# ETH_module.net
KiCad netlist of a schematic drawn in EAGLE
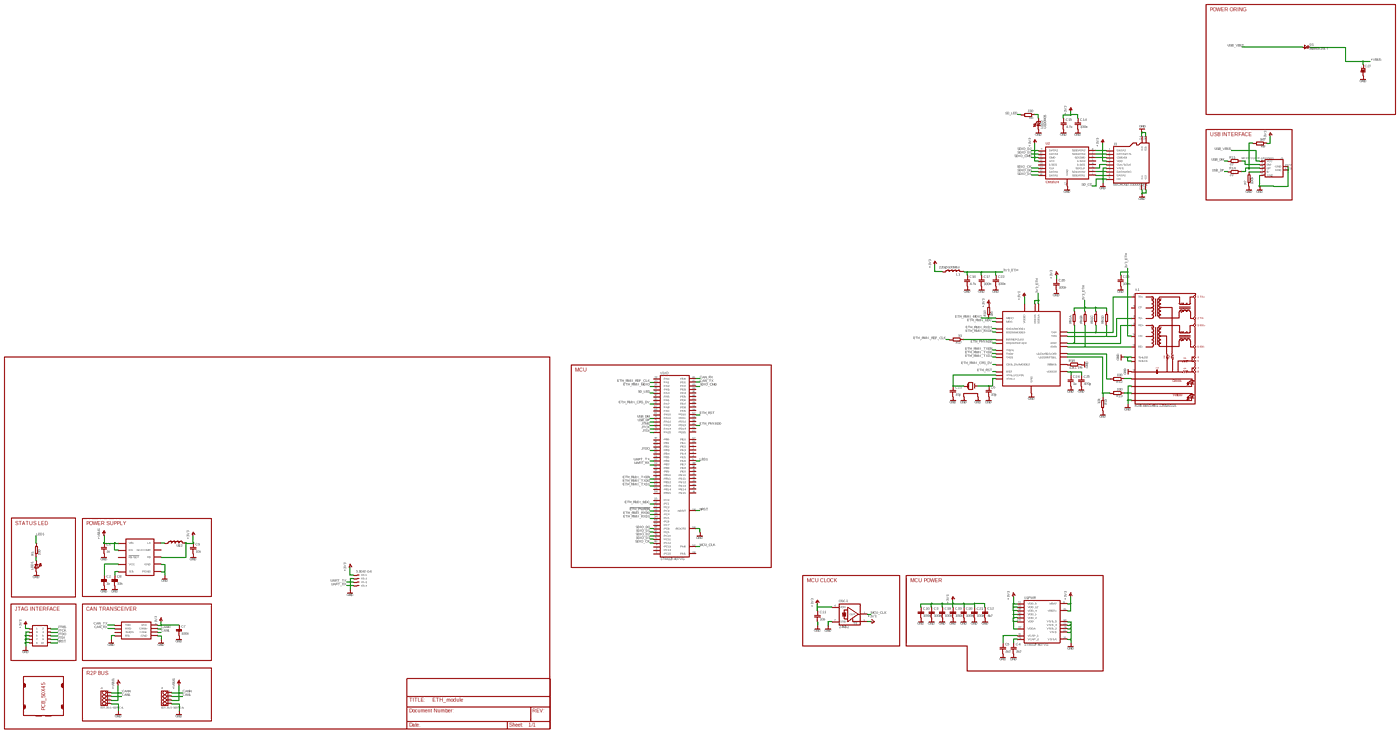
[diagram p0: schematic, sheet 1, overview]
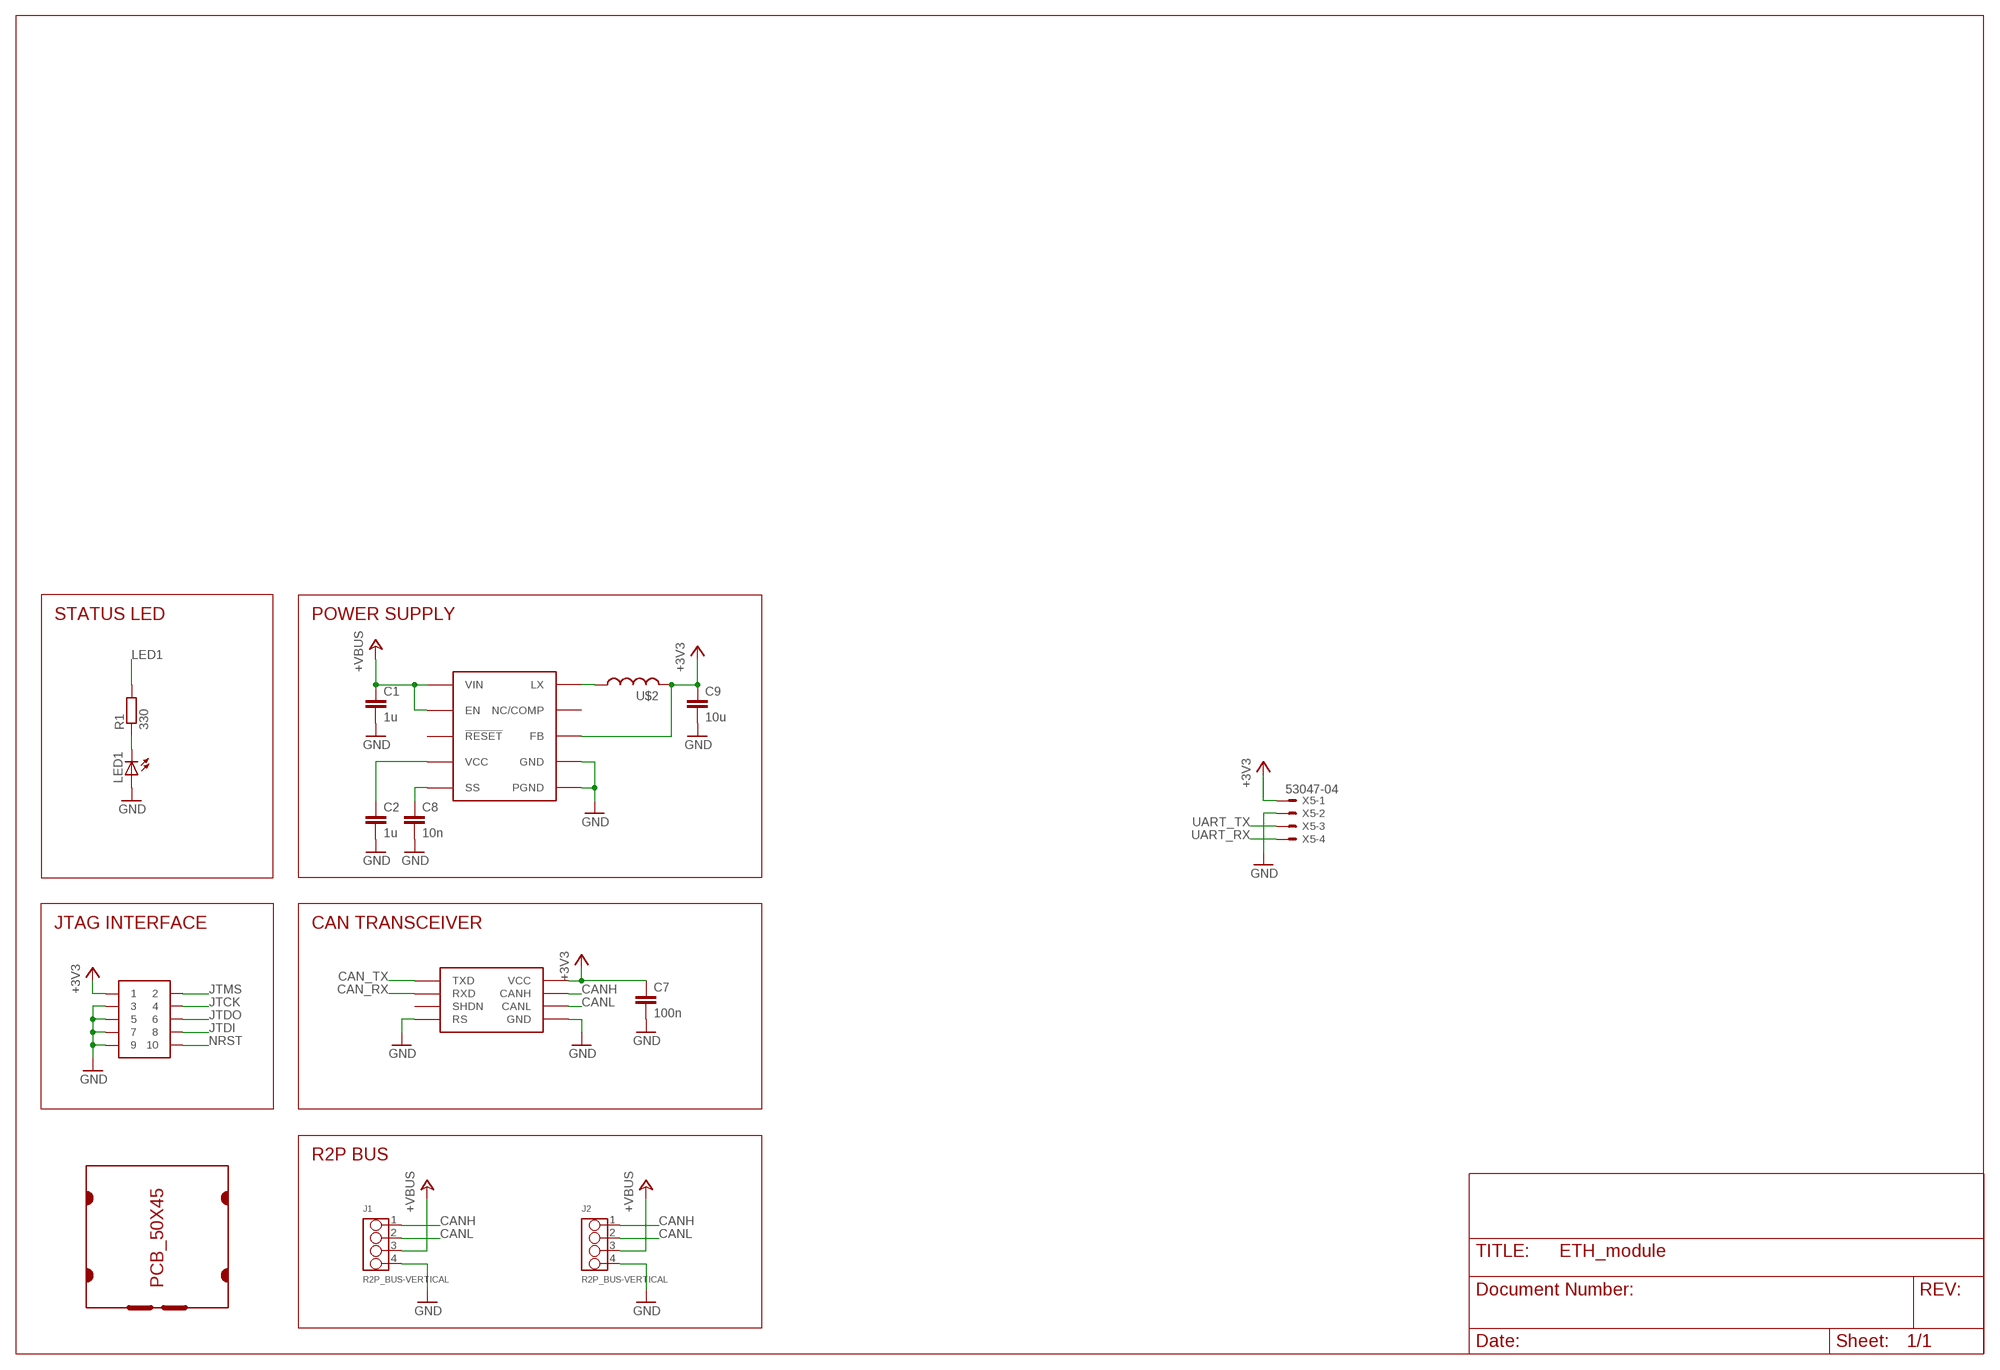
[diagram p1: schematic, sheet 1, part 1 of 4]
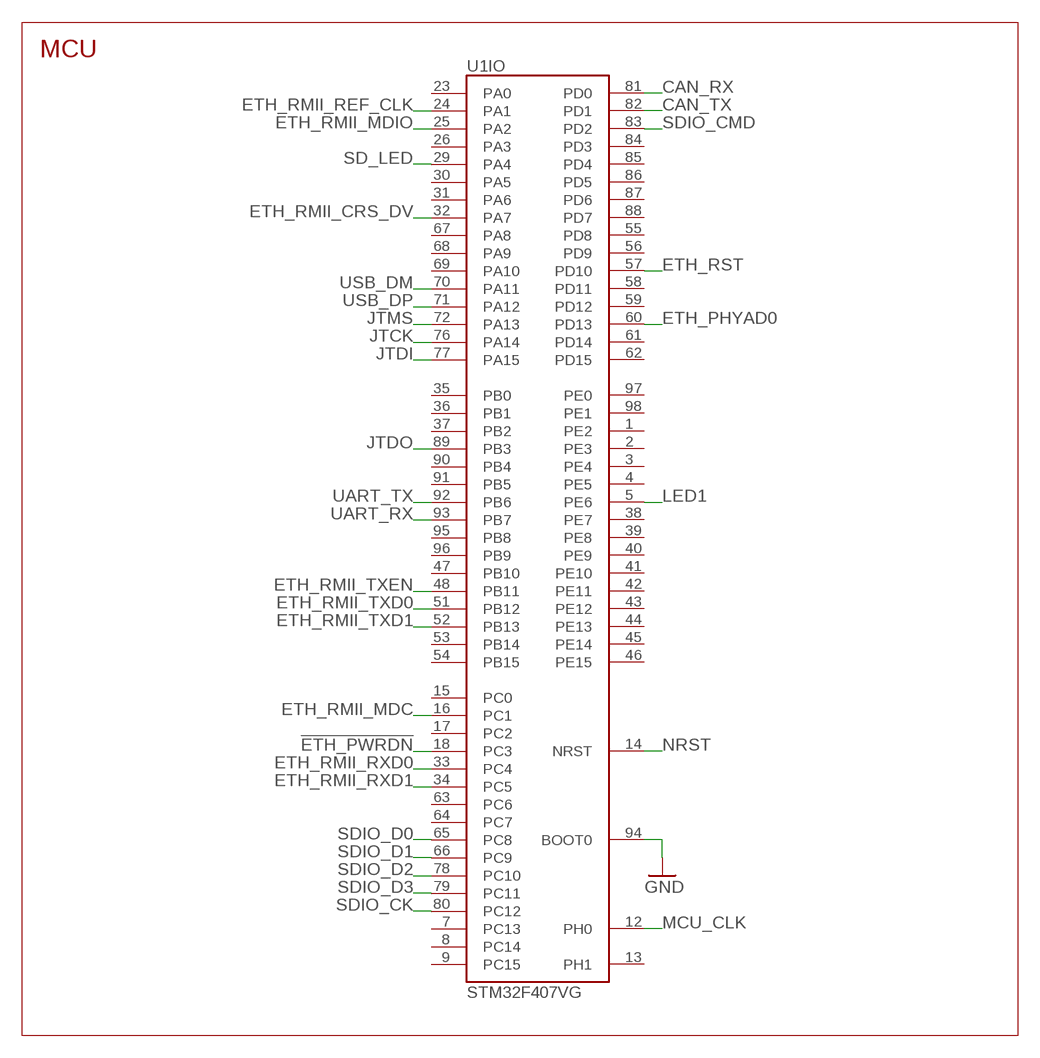
[diagram p2: schematic, sheet 1, part 2 of 4]
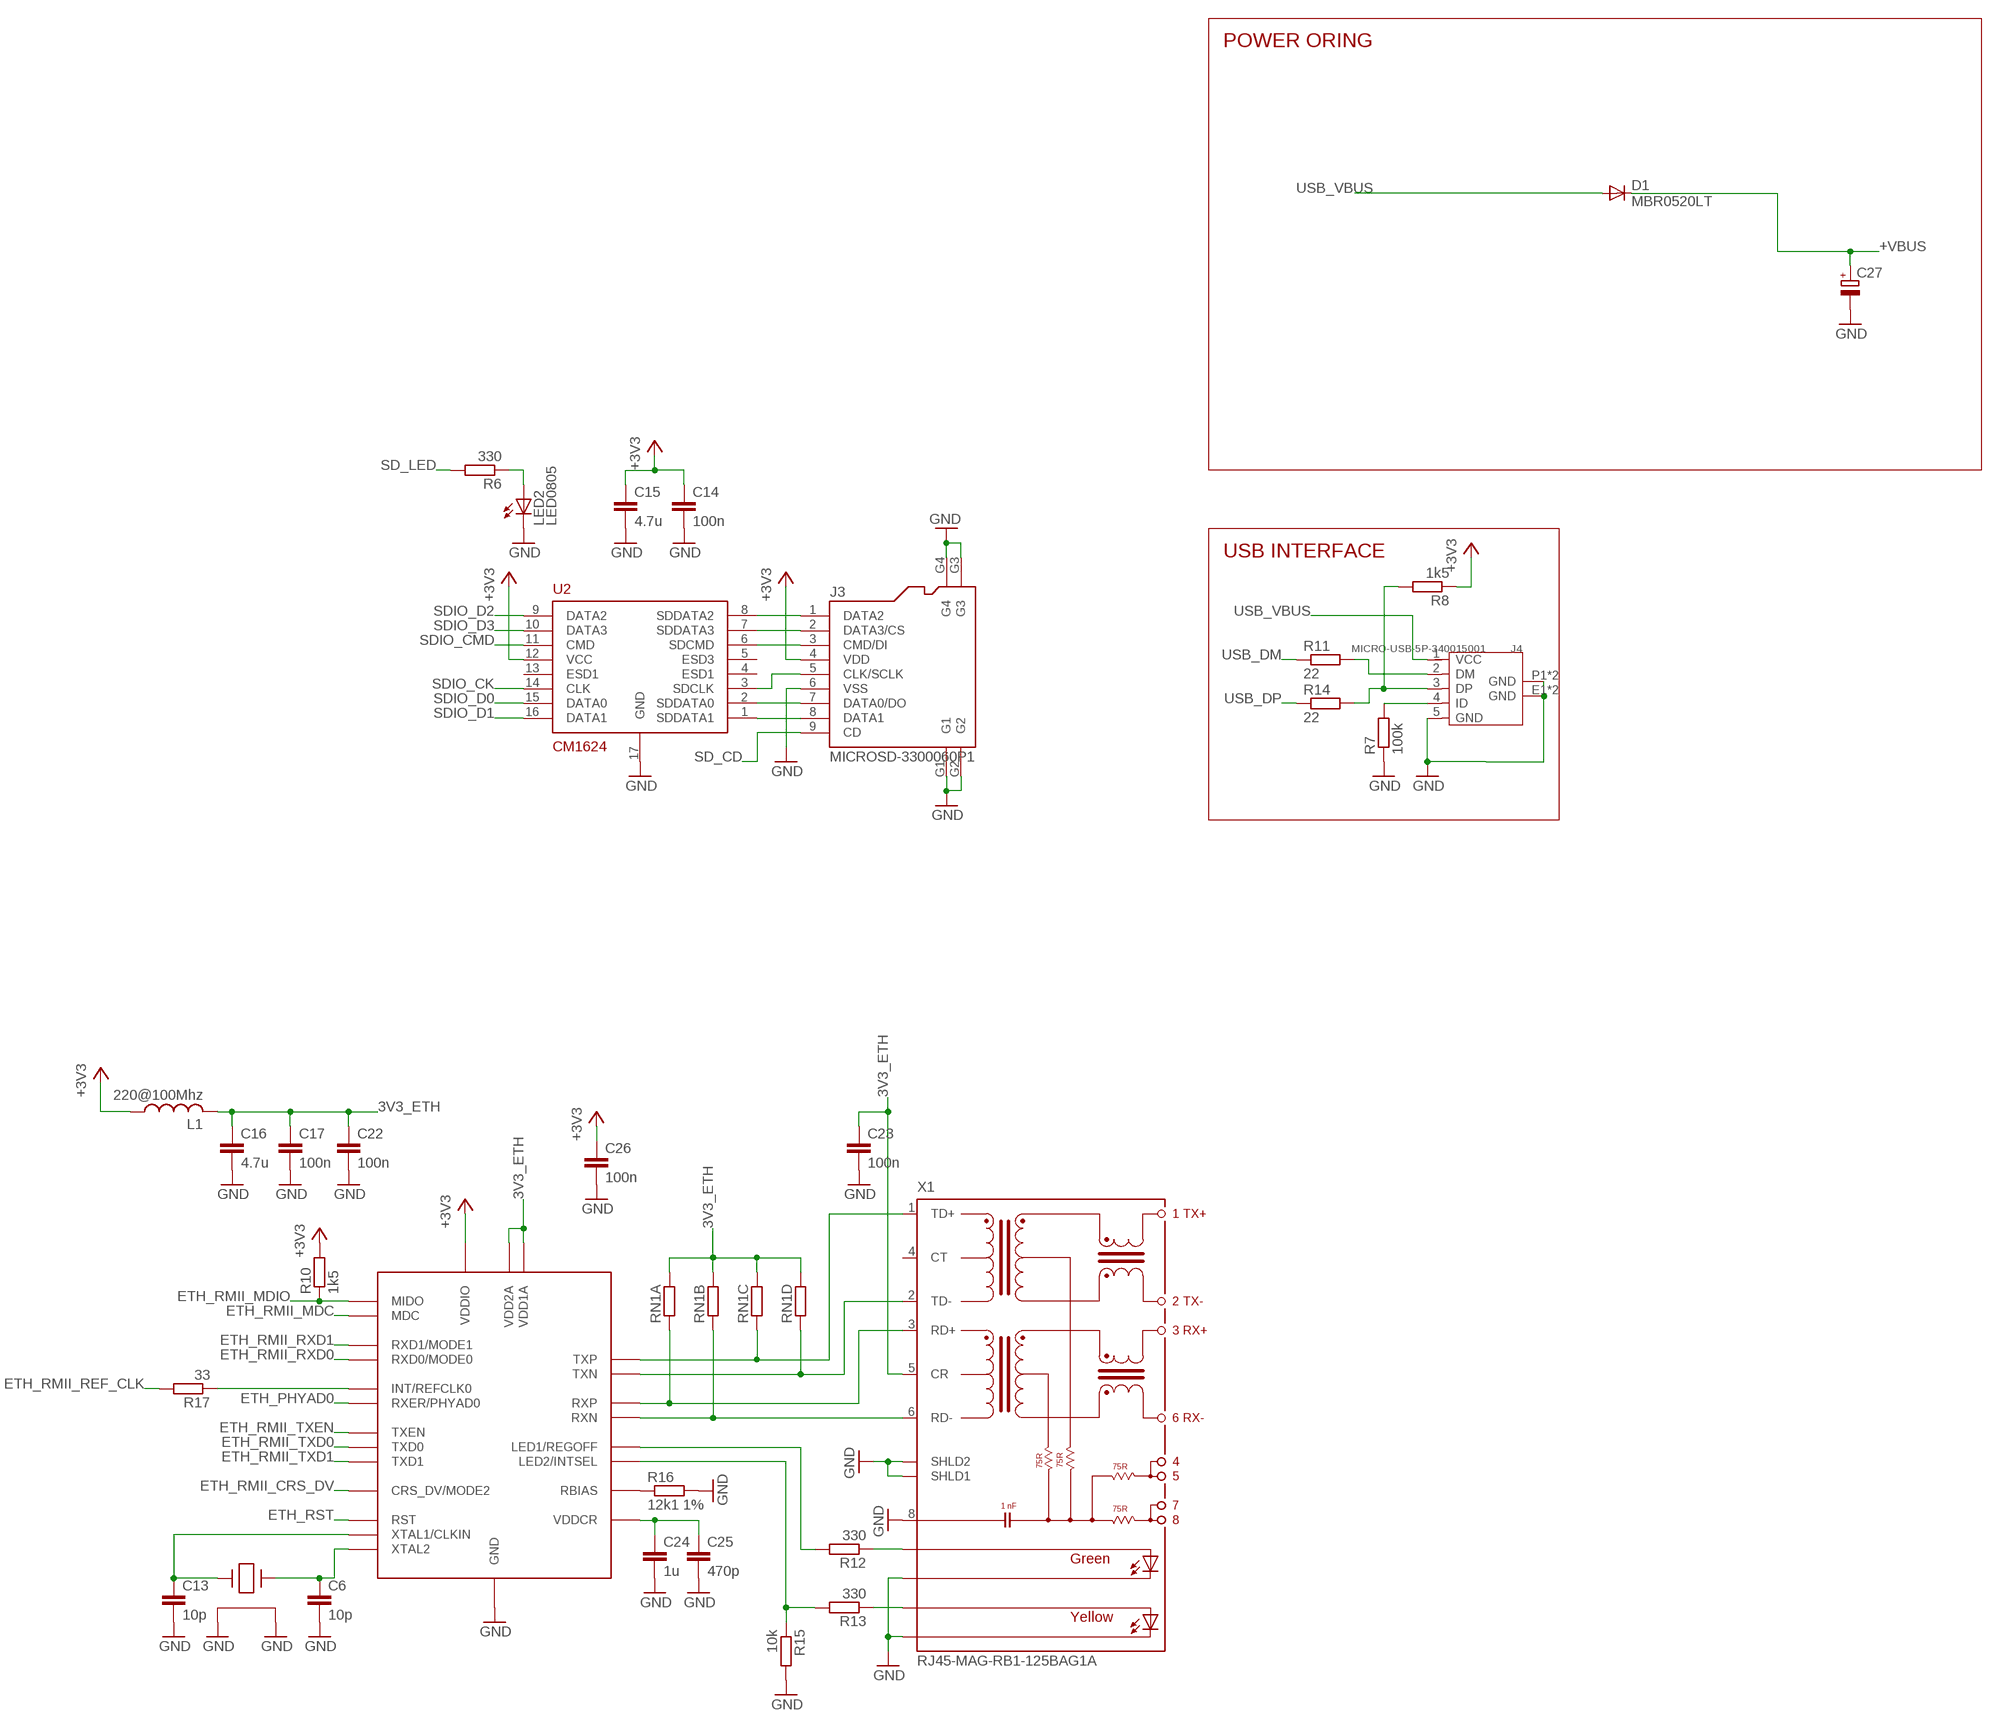
[diagram p3: schematic, sheet 1, part 3 of 4]
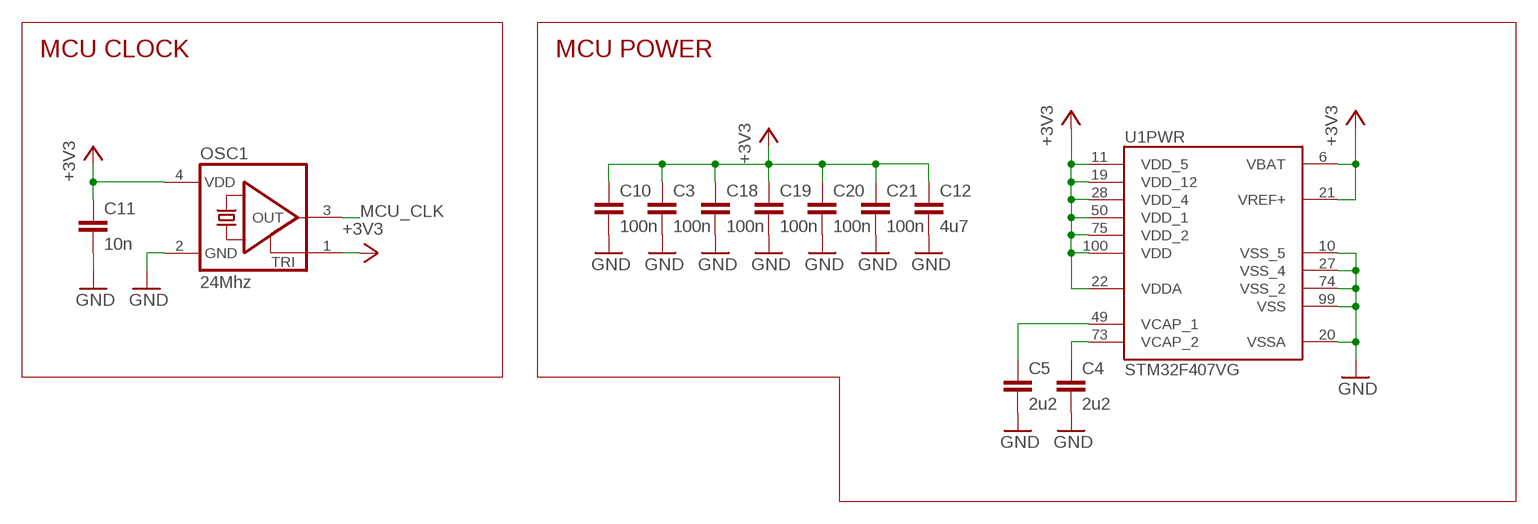
[diagram p4: schematic, sheet 1, part 4 of 4]

(export (version "E")
  (design (tool "Eeschema 10.0.6"))
  (components
    (comp (ref "C1")
      (value "1u")
      (footprint "eagle-import:C1206")
      (libsource (lib "eagle-import") (part "C1206"))
    )
    (comp (ref "C2")
      (value "1u")
      (footprint "eagle-import:C0603")
      (libsource (lib "eagle-import") (part "C0603"))
    )
    (comp (ref "C3")
      (value "100n")
      (footprint "eagle-import:C0603")
      (libsource (lib "eagle-import") (part "C0603"))
    )
    (comp (ref "C4")
      (value "2u2")
      (footprint "eagle-import:C0603")
      (libsource (lib "eagle-import") (part "C0603"))
    )
    (comp (ref "C5")
      (value "2u2")
      (footprint "eagle-import:C0603")
      (libsource (lib "eagle-import") (part "C0603"))
    )
    (comp (ref "C6")
      (value "10p")
      (footprint "eagle-import:C0603")
      (libsource (lib "eagle-import") (part "C0603"))
    )
    (comp (ref "C7")
      (value "100n")
      (footprint "eagle-import:C0603")
      (libsource (lib "eagle-import") (part "C0603"))
    )
    (comp (ref "C8")
      (value "10n")
      (footprint "eagle-import:C0603")
      (libsource (lib "eagle-import") (part "C0603"))
    )
    (comp (ref "C9")
      (value "10u")
      (footprint "eagle-import:C0805")
      (libsource (lib "eagle-import") (part "C0805"))
    )
    (comp (ref "C10")
      (value "100n")
      (footprint "eagle-import:C0603")
      (libsource (lib "eagle-import") (part "C0603"))
    )
    (comp (ref "C11")
      (value "10n")
      (footprint "eagle-import:C0603")
      (libsource (lib "eagle-import") (part "C0603"))
    )
    (comp (ref "C12")
      (value "4u7")
      (footprint "eagle-import:C0805")
      (libsource (lib "eagle-import") (part "C0805"))
    )
    (comp (ref "C13")
      (value "10p")
      (footprint "eagle-import:C0603")
      (libsource (lib "eagle-import") (part "C0603"))
    )
    (comp (ref "C14")
      (value "100n")
      (footprint "eagle-import:C0603")
      (libsource (lib "eagle-import") (part "C0603"))
    )
    (comp (ref "C15")
      (value "4.7u")
      (footprint "eagle-import:C0805")
      (libsource (lib "eagle-import") (part "C0805"))
    )
    (comp (ref "C16")
      (value "4.7u")
      (footprint "eagle-import:C0805")
      (libsource (lib "eagle-import") (part "C0805"))
    )
    (comp (ref "C17")
      (value "100n")
      (footprint "eagle-import:C0603")
      (libsource (lib "eagle-import") (part "C0603"))
    )
    (comp (ref "C18")
      (value "100n")
      (footprint "eagle-import:C0603")
      (libsource (lib "eagle-import") (part "C0603"))
    )
    (comp (ref "C19")
      (value "100n")
      (footprint "eagle-import:C0603")
      (libsource (lib "eagle-import") (part "C0603"))
    )
    (comp (ref "C20")
      (value "100n")
      (footprint "eagle-import:C0603")
      (libsource (lib "eagle-import") (part "C0603"))
    )
    (comp (ref "C21")
      (value "100n")
      (footprint "eagle-import:C0603")
      (libsource (lib "eagle-import") (part "C0603"))
    )
    (comp (ref "C22")
      (value "100n")
      (footprint "eagle-import:C0603")
      (libsource (lib "eagle-import") (part "C0603"))
    )
    (comp (ref "C23")
      (value "100n")
      (footprint "eagle-import:C0603")
      (libsource (lib "eagle-import") (part "C0603"))
    )
    (comp (ref "C24")
      (value "1u")
      (footprint "eagle-import:C0603")
      (libsource (lib "eagle-import") (part "C0603"))
    )
    (comp (ref "C25")
      (value "470p")
      (footprint "eagle-import:C0603")
      (libsource (lib "eagle-import") (part "C0603"))
    )
    (comp (ref "C26")
      (value "100n")
      (footprint "eagle-import:C0603")
      (libsource (lib "eagle-import") (part "C0603"))
    )
    (comp (ref "C27")
      (value "CPOL-EUB/3528-21R")
      (footprint "eagle-import:B_3528-21R")
      (libsource (lib "eagle-import") (part "CPOL-EUB/3528-21R"))
    )
    (comp (ref "D1")
      (value "MBR0520LT")
      (footprint "eagle-import:SOD123")
      (libsource (lib "eagle-import") (part "MBR0520LT"))
    )
    (comp (ref "J1")
      (value "R2P_BUS-VERTICAL")
      (footprint "eagle-import:OPL-EAGLE-LIBRARY_4P-2.0")
      (libsource (lib "eagle-import") (part "R2P_BUS-VERTICAL"))
    )
    (comp (ref "J2")
      (value "R2P_BUS-VERTICAL")
      (footprint "eagle-import:OPL-EAGLE-LIBRARY_4P-2.0")
      (libsource (lib "eagle-import") (part "R2P_BUS-VERTICAL"))
    )
    (comp (ref "J3")
      (value "MICROSD-3300060P1")
      (footprint "eagle-import:9P-SMD-W-RING")
      (libsource (lib "eagle-import") (part "MICROSD-3300060P1"))
    )
    (comp (ref "J4")
      (value "MICRO-USB-5P-340015001")
      (footprint "eagle-import:B-SMD-5P")
      (libsource (lib "eagle-import") (part "MICRO-USB-5P-340015001"))
    )
    (comp (ref "L1")
      (value "220@100Mhz")
      (footprint "eagle-import:L0603")
      (libsource (lib "eagle-import") (part "L0603"))
    )
    (comp (ref "LED1")
      (value "LED0805")
      (footprint "eagle-import:CHIPLED_0805")
      (libsource (lib "eagle-import") (part "LED0805"))
    )
    (comp (ref "LED2")
      (value "LED0805")
      (footprint "eagle-import:CHIPLED_0805")
      (libsource (lib "eagle-import") (part "LED0805"))
    )
    (comp (ref "OSC1")
      (value "24Mhz")
      (footprint "eagle-import:XTAL_2.5X2")
      (libsource (lib "eagle-import") (part "OSC"))
    )
    (comp (ref "R1")
      (value "330")
      (footprint "eagle-import:R0603")
      (libsource (lib "eagle-import") (part "R0603"))
    )
    (comp (ref "R6")
      (value "330")
      (footprint "eagle-import:R0603")
      (libsource (lib "eagle-import") (part "R0603"))
    )
    (comp (ref "R7")
      (value "100k")
      (footprint "eagle-import:R0603")
      (libsource (lib "eagle-import") (part "R0603"))
    )
    (comp (ref "R8")
      (value "1k5")
      (footprint "eagle-import:R0603")
      (libsource (lib "eagle-import") (part "R0603"))
    )
    (comp (ref "R10")
      (value "1k5")
      (footprint "eagle-import:R0603")
      (libsource (lib "eagle-import") (part "R0603"))
    )
    (comp (ref "R11")
      (value "22")
      (footprint "eagle-import:R0603")
      (libsource (lib "eagle-import") (part "R0603"))
    )
    (comp (ref "R12")
      (value "330")
      (footprint "eagle-import:R0603")
      (libsource (lib "eagle-import") (part "R0603"))
    )
    (comp (ref "R13")
      (value "330")
      (footprint "eagle-import:R0603")
      (libsource (lib "eagle-import") (part "R0603"))
    )
    (comp (ref "R14")
      (value "22")
      (footprint "eagle-import:R0603")
      (libsource (lib "eagle-import") (part "R0603"))
    )
    (comp (ref "R15")
      (value "10k")
      (footprint "eagle-import:R0603")
      (libsource (lib "eagle-import") (part "R0603"))
    )
    (comp (ref "R16")
      (value "12k1 1%")
      (footprint "eagle-import:R0603")
      (libsource (lib "eagle-import") (part "R0603"))
    )
    (comp (ref "R17")
      (value "33")
      (footprint "eagle-import:R0603")
      (libsource (lib "eagle-import") (part "R0603"))
    )
    (comp (ref "RN1")
      (value "RNETWORK_4-1206")
      (footprint "eagle-import:RNET4_1206")
      (libsource (lib "eagle-import") (part "RNETWORK_4-1206"))
    )
    (comp (ref "SOT1")
      (value "MAX3051EKA")
      (footprint "eagle-import:SOT23-8L")
      (libsource (lib "eagle-import") (part "MAX3051EKA"))
    )
    (comp (ref "U$1")
      (value "PCB_50X45")
      (footprint "eagle-import:50X45")
      (libsource (lib "eagle-import") (part "PCB_50X45"))
    )
    (comp (ref "U$2")
      (value "LPS4018")
      (footprint "eagle-import:COILCRAFT_LPS4018")
      (libsource (lib "eagle-import") (part "LPS4018"))
    )
    (comp (ref "U$3")
      (value "MAX17501")
      (footprint "eagle-import:TDFN-10")
      (libsource (lib "eagle-import") (part "MAX17501"))
    )
    (comp (ref "U$4")
      (value "JTAG-TH")
      (footprint "eagle-import:SAMTEC_FTSH-105-TH")
      (libsource (lib "eagle-import") (part "JTAG-TH"))
    )
    (comp (ref "U$5")
      (value "LAN8720A")
      (footprint "eagle-import:QFN24")
      (libsource (lib "eagle-import") (part "LAN8720A"))
    )
    (comp (ref "U$6")
      (value "XTAL-2.5X2")
      (footprint "eagle-import:XTAL_2.5X2")
      (libsource (lib "eagle-import") (part "XTAL-2.5X2"))
    )
    (comp (ref "U1")
      (value "STM32F407VG")
      (footprint "eagle-import:LQFP100")
      (libsource (lib "eagle-import") (part "STM32F407VG"))
    )
    (comp (ref "U2")
      (value "CM1624")
      (footprint "eagle-import:UDFN16")
      (libsource (lib "eagle-import") (part "CM1624"))
    )
    (comp (ref "X1")
      (value "RJ45-MAG-RB1-125BAG1A")
      (footprint "eagle-import:WIZNET_RB1-125BAG1A")
      (libsource (lib "eagle-import") (part "RJ45-MAG-RB1-125BAG1A"))
    )
    (comp (ref "X5")
      (value "53047-04")
      (footprint "eagle-import:53047-04")
      (fields (field (name "MF") "WALDOM/MOLEX") (field (name "MPN") "53047-0410"))
      (libsource (lib "eagle-import") (part "53?-04047"))
    )
  )
  (nets
    (net (code "1") (name "+3V3") (class "Default")
      (node (ref "C10") (pin "1") (pinfunction "1_1") (pintype "passive"))
      (node (ref "C11") (pin "1") (pinfunction "1_1") (pintype "passive"))
      (node (ref "C12") (pin "1") (pinfunction "1_1") (pintype "passive"))
      (node (ref "C14") (pin "1") (pinfunction "1_1") (pintype "passive"))
      (node (ref "C15") (pin "1") (pinfunction "1_1") (pintype "passive"))
      (node (ref "C18") (pin "1") (pinfunction "1_1") (pintype "passive"))
      (node (ref "C19") (pin "1") (pinfunction "1_1") (pintype "passive"))
      (node (ref "C20") (pin "1") (pinfunction "1_1") (pintype "passive"))
      (node (ref "C21") (pin "1") (pinfunction "1_1") (pintype "passive"))
      (node (ref "C26") (pin "1") (pinfunction "1_1") (pintype "passive"))
      (node (ref "C3") (pin "1") (pinfunction "1_1") (pintype "passive"))
      (node (ref "C7") (pin "1") (pinfunction "1_1") (pintype "passive"))
      (node (ref "C9") (pin "1") (pinfunction "1_1") (pintype "passive"))
      (node (ref "J3") (pin "4") (pinfunction "VDD_4") (pintype "bidirectional"))
      (node (ref "L1") (pin "1") (pinfunction "1_1") (pintype "passive"))
      (node (ref "OSC1") (pin "1") (pinfunction "TRI_1") (pintype "input"))
      (node (ref "OSC1") (pin "4") (pinfunction "VDD_4") (pintype "power_in"))
      (node (ref "R10") (pin "2") (pinfunction "2_2") (pintype "passive"))
      (node (ref "R8") (pin "1") (pinfunction "1_1") (pintype "passive"))
      (node (ref "SOT1") (pin "3") (pinfunction "VCC_3") (pintype "bidirectional"))
      (node (ref "U$2") (pin "P$2") (pinfunction "2_P$2") (pintype "passive"))
      (node (ref "U$3") (pin "P$5") (pinfunction "FB_P$5") (pintype "bidirectional"))
      (node (ref "U$4") (pin "1") (pinfunction "1_1") (pintype "bidirectional"))
      (node (ref "U$5") (pin "P$9") (pinfunction "VDDIO_P$9") (pintype "bidirectional"))
      (node (ref "U1") (pin "100") (pinfunction "VDD_100") (pintype "power_in"))
      (node (ref "U1") (pin "11") (pinfunction "VDD_5_11") (pintype "power_in"))
      (node (ref "U1") (pin "19") (pinfunction "VDD_12_19") (pintype "power_in"))
      (node (ref "U1") (pin "21") (pinfunction "VREF+_21") (pintype "passive"))
      (node (ref "U1") (pin "22") (pinfunction "VDDA_22") (pintype "power_in"))
      (node (ref "U1") (pin "28") (pinfunction "VDD_4_28") (pintype "power_in"))
      (node (ref "U1") (pin "50") (pinfunction "VDD_1_50") (pintype "power_in"))
      (node (ref "U1") (pin "6") (pinfunction "VBAT_6") (pintype "power_in"))
      (node (ref "U1") (pin "75") (pinfunction "VDD_2_75") (pintype "power_in"))
      (node (ref "U2") (pin "12") (pinfunction "VCC_12") (pintype "bidirectional"))
      (node (ref "X5") (pin "1") (pinfunction "S_1") (pintype "passive"))
    )
    (net (code "2") (name "+VBUS") (class "Default")
      (node (ref "C1") (pin "1") (pinfunction "1_1") (pintype "passive"))
      (node (ref "C27") (pin "+") (pinfunction "+_+") (pintype "passive"))
      (node (ref "D1") (pin "C") (pinfunction "C_C") (pintype "passive"))
      (node (ref "J1") (pin "3") (pinfunction "3_3") (pintype "bidirectional"))
      (node (ref "J2") (pin "3") (pinfunction "3_3") (pintype "bidirectional"))
      (node (ref "U$3") (pin "P$2") (pinfunction "VIN_P$2") (pintype "bidirectional"))
      (node (ref "U$3") (pin "P$3") (pinfunction "EN_P$3") (pintype "bidirectional"))
    )
    (net (code "3") (name "/3V3_ETH") (class "Default")
      (node (ref "C16") (pin "1") (pinfunction "1_1") (pintype "passive"))
      (node (ref "C17") (pin "1") (pinfunction "1_1") (pintype "passive"))
      (node (ref "C22") (pin "1") (pinfunction "1_1") (pintype "passive"))
      (node (ref "C23") (pin "1") (pinfunction "1_1") (pintype "passive"))
      (node (ref "L1") (pin "2") (pinfunction "2_2") (pintype "passive"))
      (node (ref "RN1") (pin "5") (pinfunction "2_5") (pintype "passive"))
      (node (ref "RN1") (pin "6") (pinfunction "2_6") (pintype "passive"))
      (node (ref "RN1") (pin "7") (pinfunction "2_7") (pintype "passive"))
      (node (ref "RN1") (pin "8") (pinfunction "2_8") (pintype "passive"))
      (node (ref "U$5") (pin "P$1") (pinfunction "VDD2A_P$1") (pintype "bidirectional"))
      (node (ref "U$5") (pin "P$19") (pinfunction "VDD1A_P$19") (pintype "bidirectional"))
      (node (ref "X1") (pin "5") (pinfunction "CR_5") (pintype "passive"))
    )
    (net (code "4") (name "/CANH") (class "Default")
      (node (ref "J1") (pin "1") (pinfunction "1_1") (pintype "bidirectional"))
      (node (ref "J2") (pin "1") (pinfunction "1_1") (pintype "bidirectional"))
      (node (ref "SOT1") (pin "7") (pinfunction "CANH_7") (pintype "bidirectional"))
    )
    (net (code "5") (name "/CANL") (class "Default")
      (node (ref "J1") (pin "2") (pinfunction "2_2") (pintype "bidirectional"))
      (node (ref "J2") (pin "2") (pinfunction "2_2") (pintype "bidirectional"))
      (node (ref "SOT1") (pin "6") (pinfunction "CANL_6") (pintype "bidirectional"))
    )
    (net (code "6") (name "/CAN_RX") (class "Default")
      (node (ref "SOT1") (pin "4") (pinfunction "RXD_4") (pintype "bidirectional"))
      (node (ref "U1") (pin "81") (pinfunction "PD0_81") (pintype "passive"))
    )
    (net (code "7") (name "/CAN_TX") (class "Default")
      (node (ref "SOT1") (pin "1") (pinfunction "TXD_1") (pintype "bidirectional"))
      (node (ref "U1") (pin "82") (pinfunction "PD1_82") (pintype "passive"))
    )
    (net (code "8") (name "/ETH_PHYAD0") (class "Default")
      (node (ref "U$5") (pin "P$10") (pinfunction "RXER/PHYAD0_P$10") (pintype "bidirectional"))
      (node (ref "U1") (pin "60") (pinfunction "PD13_60") (pintype "passive"))
    )
    (net (code "9") (name "/ETH_RMII_CRS_DV") (class "Default")
      (node (ref "U$5") (pin "P$11") (pinfunction "CRS_DV/MODE2_P$11") (pintype "bidirectional"))
      (node (ref "U1") (pin "32") (pinfunction "PA7_32") (pintype "passive"))
    )
    (net (code "10") (name "/ETH_RMII_MDC") (class "Default")
      (node (ref "U$5") (pin "P$13") (pinfunction "MDC_P$13") (pintype "bidirectional"))
      (node (ref "U1") (pin "16") (pinfunction "PC1_16") (pintype "passive"))
    )
    (net (code "11") (name "/ETH_RMII_MDIO") (class "Default")
      (node (ref "R10") (pin "1") (pinfunction "1_1") (pintype "passive"))
      (node (ref "U$5") (pin "P$12") (pinfunction "MIDO_P$12") (pintype "bidirectional"))
      (node (ref "U1") (pin "25") (pinfunction "PA2_25") (pintype "passive"))
    )
    (net (code "12") (name "/ETH_RMII_REF_CLK") (class "Default")
      (node (ref "R17") (pin "2") (pinfunction "2_2") (pintype "passive"))
      (node (ref "U1") (pin "24") (pinfunction "PA1_24") (pintype "passive"))
    )
    (net (code "13") (name "/ETH_RMII_RXD0") (class "Default")
      (node (ref "U$5") (pin "P$8") (pinfunction "RXD0/MODE0_P$8") (pintype "bidirectional"))
      (node (ref "U1") (pin "33") (pinfunction "PC4_33") (pintype "passive"))
    )
    (net (code "14") (name "/ETH_RMII_RXD1") (class "Default")
      (node (ref "U$5") (pin "P$7") (pinfunction "RXD1/MODE1_P$7") (pintype "bidirectional"))
      (node (ref "U1") (pin "34") (pinfunction "PC5_34") (pintype "passive"))
    )
    (net (code "15") (name "/ETH_RMII_TXD0") (class "Default")
      (node (ref "U$5") (pin "P$17") (pinfunction "TXD0_P$17") (pintype "bidirectional"))
      (node (ref "U1") (pin "51") (pinfunction "PB12_51") (pintype "passive"))
    )
    (net (code "16") (name "/ETH_RMII_TXD1") (class "Default")
      (node (ref "U$5") (pin "P$18") (pinfunction "TXD1_P$18") (pintype "bidirectional"))
      (node (ref "U1") (pin "52") (pinfunction "PB13_52") (pintype "passive"))
    )
    (net (code "17") (name "/ETH_RMII_TXEN") (class "Default")
      (node (ref "U$5") (pin "P$16") (pinfunction "TXEN_P$16") (pintype "bidirectional"))
      (node (ref "U1") (pin "48") (pinfunction "PB11_48") (pintype "passive"))
    )
    (net (code "18") (name "/ETH_RST") (class "Default")
      (node (ref "U$5") (pin "P$15") (pinfunction "RST_P$15") (pintype "bidirectional"))
      (node (ref "U1") (pin "57") (pinfunction "PD10_57") (pintype "passive"))
    )
    (net (code "19") (name "/JTCK") (class "Default")
      (node (ref "U$4") (pin "4") (pinfunction "4_4") (pintype "bidirectional"))
      (node (ref "U1") (pin "76") (pinfunction "PA14_76") (pintype "passive"))
    )
    (net (code "20") (name "/JTDI") (class "Default")
      (node (ref "U$4") (pin "8") (pinfunction "8_8") (pintype "bidirectional"))
      (node (ref "U1") (pin "77") (pinfunction "PA15_77") (pintype "passive"))
    )
    (net (code "21") (name "/JTDO") (class "Default")
      (node (ref "U$4") (pin "6") (pinfunction "6_6") (pintype "bidirectional"))
      (node (ref "U1") (pin "89") (pinfunction "PB3_89") (pintype "passive"))
    )
    (net (code "22") (name "/JTMS") (class "Default")
      (node (ref "U$4") (pin "2") (pinfunction "2_2") (pintype "bidirectional"))
      (node (ref "U1") (pin "72") (pinfunction "PA13_72") (pintype "passive"))
    )
    (net (code "23") (name "/LED1") (class "Default")
      (node (ref "R1") (pin "2") (pinfunction "2_2") (pintype "passive"))
      (node (ref "U1") (pin "5") (pinfunction "PE6_5") (pintype "passive"))
    )
    (net (code "24") (name "/MCU_CLK") (class "Default")
      (node (ref "OSC1") (pin "3") (pinfunction "OUT_3") (pintype "output"))
      (node (ref "U1") (pin "12") (pinfunction "PH0_12") (pintype "passive"))
    )
    (net (code "25") (name "/NRST") (class "Default")
      (node (ref "U$4") (pin "10") (pinfunction "10_10") (pintype "bidirectional"))
      (node (ref "U1") (pin "14") (pinfunction "NRST_14") (pintype "passive"))
    )
    (net (code "26") (name "/SDIO_CK") (class "Default")
      (node (ref "U1") (pin "80") (pinfunction "PC12_80") (pintype "passive"))
      (node (ref "U2") (pin "14") (pinfunction "CLK_14") (pintype "bidirectional"))
    )
    (net (code "27") (name "/SDIO_CMD") (class "Default")
      (node (ref "U1") (pin "83") (pinfunction "PD2_83") (pintype "passive"))
      (node (ref "U2") (pin "11") (pinfunction "CMD_11") (pintype "bidirectional"))
    )
    (net (code "28") (name "/SDIO_D0") (class "Default")
      (node (ref "U1") (pin "65") (pinfunction "PC8_65") (pintype "passive"))
      (node (ref "U2") (pin "15") (pinfunction "DATA0_15") (pintype "bidirectional"))
    )
    (net (code "29") (name "/SDIO_D1") (class "Default")
      (node (ref "U1") (pin "66") (pinfunction "PC9_66") (pintype "passive"))
      (node (ref "U2") (pin "16") (pinfunction "DATA1_16") (pintype "bidirectional"))
    )
    (net (code "30") (name "/SDIO_D2") (class "Default")
      (node (ref "U1") (pin "78") (pinfunction "PC10_78") (pintype "passive"))
      (node (ref "U2") (pin "9") (pinfunction "DATA2_9") (pintype "bidirectional"))
    )
    (net (code "31") (name "/SDIO_D3") (class "Default")
      (node (ref "U1") (pin "79") (pinfunction "PC11_79") (pintype "passive"))
      (node (ref "U2") (pin "10") (pinfunction "DATA3_10") (pintype "bidirectional"))
    )
    (net (code "32") (name "/SD_CD") (class "Default")
      (node (ref "J3") (pin "9") (pinfunction "CD_9") (pintype "bidirectional"))
    )
    (net (code "33") (name "/SD_LED") (class "Default")
      (node (ref "R6") (pin "2") (pinfunction "2_2") (pintype "passive"))
      (node (ref "U1") (pin "29") (pinfunction "PA4_29") (pintype "passive"))
    )
    (net (code "34") (name "/UART_RX") (class "Default")
      (node (ref "U1") (pin "93") (pinfunction "PB7_93") (pintype "passive"))
      (node (ref "X5") (pin "4") (pinfunction "S_4") (pintype "passive"))
    )
    (net (code "35") (name "/UART_TX") (class "Default")
      (node (ref "U1") (pin "92") (pinfunction "PB6_92") (pintype "passive"))
      (node (ref "X5") (pin "3") (pinfunction "S_3") (pintype "passive"))
    )
    (net (code "36") (name "/USB_DM") (class "Default")
      (node (ref "R11") (pin "1") (pinfunction "1_1") (pintype "passive"))
      (node (ref "U1") (pin "70") (pinfunction "PA11_70") (pintype "passive"))
    )
    (net (code "37") (name "/USB_DP") (class "Default")
      (node (ref "R14") (pin "1") (pinfunction "1_1") (pintype "passive"))
      (node (ref "U1") (pin "71") (pinfunction "PA12_71") (pintype "passive"))
    )
    (net (code "38") (name "/USB_VBUS") (class "Default")
      (node (ref "D1") (pin "A") (pinfunction "A_A") (pintype "passive"))
      (node (ref "J4") (pin "1") (pinfunction "VCC_1") (pintype "bidirectional"))
    )
    (net (code "39") (name "/~{ETH_PWRDN}") (class "Default")
      (node (ref "U1") (pin "18") (pinfunction "PC3_18") (pintype "passive"))
    )
    (net (code "40") (name "GND") (class "Default")
      (node (ref "C1") (pin "2") (pinfunction "2_2") (pintype "passive"))
      (node (ref "C10") (pin "2") (pinfunction "2_2") (pintype "passive"))
      (node (ref "C11") (pin "2") (pinfunction "2_2") (pintype "passive"))
      (node (ref "C12") (pin "2") (pinfunction "2_2") (pintype "passive"))
      (node (ref "C13") (pin "2") (pinfunction "2_2") (pintype "passive"))
      (node (ref "C14") (pin "2") (pinfunction "2_2") (pintype "passive"))
      (node (ref "C15") (pin "2") (pinfunction "2_2") (pintype "passive"))
      (node (ref "C16") (pin "2") (pinfunction "2_2") (pintype "passive"))
      (node (ref "C17") (pin "2") (pinfunction "2_2") (pintype "passive"))
      (node (ref "C18") (pin "2") (pinfunction "2_2") (pintype "passive"))
      (node (ref "C19") (pin "2") (pinfunction "2_2") (pintype "passive"))
      (node (ref "C2") (pin "2") (pinfunction "2_2") (pintype "passive"))
      (node (ref "C20") (pin "2") (pinfunction "2_2") (pintype "passive"))
      (node (ref "C21") (pin "2") (pinfunction "2_2") (pintype "passive"))
      (node (ref "C22") (pin "2") (pinfunction "2_2") (pintype "passive"))
      (node (ref "C23") (pin "2") (pinfunction "2_2") (pintype "passive"))
      (node (ref "C24") (pin "2") (pinfunction "2_2") (pintype "passive"))
      (node (ref "C25") (pin "2") (pinfunction "2_2") (pintype "passive"))
      (node (ref "C26") (pin "2") (pinfunction "2_2") (pintype "passive"))
      (node (ref "C27") (pin "-") (pinfunction "-_-") (pintype "passive"))
      (node (ref "C3") (pin "2") (pinfunction "2_2") (pintype "passive"))
      (node (ref "C4") (pin "2") (pinfunction "2_2") (pintype "passive"))
      (node (ref "C5") (pin "2") (pinfunction "2_2") (pintype "passive"))
      (node (ref "C6") (pin "2") (pinfunction "2_2") (pintype "passive"))
      (node (ref "C7") (pin "2") (pinfunction "2_2") (pintype "passive"))
      (node (ref "C8") (pin "2") (pinfunction "2_2") (pintype "passive"))
      (node (ref "C9") (pin "2") (pinfunction "2_2") (pintype "passive"))
      (node (ref "J1") (pin "4") (pinfunction "4_4") (pintype "bidirectional"))
      (node (ref "J2") (pin "4") (pinfunction "4_4") (pintype "bidirectional"))
      (node (ref "J3") (pin "6") (pinfunction "VSS_6") (pintype "bidirectional"))
      (node (ref "J3") (pin "G1") (pinfunction "G1_G1") (pintype "bidirectional"))
      (node (ref "J3") (pin "G2") (pinfunction "G2_G2") (pintype "bidirectional"))
      (node (ref "J3") (pin "G3") (pinfunction "G3_G3") (pintype "bidirectional"))
      (node (ref "J3") (pin "G4") (pinfunction "G4_G4") (pintype "bidirectional"))
      (node (ref "J4") (pin "5") (pinfunction "GND_5") (pintype "bidirectional"))
      (node (ref "J4") (pin "E1") (pinfunction "GND_E1") (pintype "bidirectional"))
      (node (ref "J4") (pin "E2") (pinfunction "GND_E2") (pintype "bidirectional"))
      (node (ref "J4") (pin "P1") (pinfunction "GND_P1") (pintype "bidirectional"))
      (node (ref "J4") (pin "P2") (pinfunction "GND_P2") (pintype "bidirectional"))
      (node (ref "LED1") (pin "A") (pinfunction "A_A") (pintype "passive"))
      (node (ref "LED2") (pin "C") (pinfunction "C_C") (pintype "passive"))
      (node (ref "OSC1") (pin "2") (pinfunction "GND_2") (pintype "power_in"))
      (node (ref "R15") (pin "2") (pinfunction "2_2") (pintype "passive"))
      (node (ref "R16") (pin "2") (pinfunction "2_2") (pintype "passive"))
      (node (ref "R7") (pin "1") (pinfunction "1_1") (pintype "passive"))
      (node (ref "SOT1") (pin "2") (pinfunction "GND_2") (pintype "bidirectional"))
      (node (ref "SOT1") (pin "8") (pinfunction "RS_8") (pintype "bidirectional"))
      (node (ref "U$3") (pin "P$1") (pinfunction "PGND_P$1") (pintype "bidirectional"))
      (node (ref "U$3") (pin "P$11") (pinfunction "PGND_P$11") (pintype "bidirectional"))
      (node (ref "U$3") (pin "P$9") (pinfunction "GND_P$9") (pintype "bidirectional"))
      (node (ref "U$4") (pin "3") (pinfunction "3_3") (pintype "bidirectional"))
      (node (ref "U$4") (pin "5") (pinfunction "5_5") (pintype "bidirectional"))
      (node (ref "U$4") (pin "7") (pinfunction "7_7") (pintype "bidirectional"))
      (node (ref "U$4") (pin "9") (pinfunction "9_9") (pintype "bidirectional"))
      (node (ref "U$5") (pin "P$25") (pinfunction "GND_P$25") (pintype "bidirectional"))
      (node (ref "U$6") (pin "2") (pinfunction "2_2") (pintype "bidirectional"))
      (node (ref "U$6") (pin "4") (pinfunction "4_4") (pintype "bidirectional"))
      (node (ref "U1") (pin "10") (pinfunction "VSS_5_10") (pintype "power_in"))
      (node (ref "U1") (pin "20") (pinfunction "VSSA_20") (pintype "power_in"))
      (node (ref "U1") (pin "27") (pinfunction "VSS_4_27") (pintype "power_in"))
      (node (ref "U1") (pin "74") (pinfunction "VSS_2_74") (pintype "power_in"))
      (node (ref "U1") (pin "94") (pinfunction "BOOT0_94") (pintype "passive"))
      (node (ref "U1") (pin "99") (pinfunction "VSS_99") (pintype "power_in"))
      (node (ref "U2") (pin "17") (pinfunction "GND_17") (pintype "bidirectional"))
      (node (ref "X1") (pin "10") (pinfunction "SHLD2_10") (pintype "passive"))
      (node (ref "X1") (pin "8") (pinfunction "8_8") (pintype "passive"))
      (node (ref "X1") (pin "9") (pinfunction "SHLD1_9") (pintype "passive"))
      (node (ref "X1") (pin "L2") (pinfunction "YK_L2") (pintype "passive"))
      (node (ref "X1") (pin "L4") (pinfunction "GK_L4") (pintype "passive"))
      (node (ref "X5") (pin "2") (pinfunction "S_2") (pintype "passive"))
    )
    (net (code "41") (name "Net-(J3-CLK{slash}SCLK)") (class "Default")
      (node (ref "J3") (pin "5") (pinfunction "CLK/SCLK_5") (pintype "bidirectional"))
      (node (ref "U2") (pin "3") (pinfunction "SDCLK_3") (pintype "bidirectional"))
    )
    (net (code "42") (name "Net-(J3-CMD{slash}DI)") (class "Default")
      (node (ref "J3") (pin "3") (pinfunction "CMD/DI_3") (pintype "bidirectional"))
      (node (ref "U2") (pin "6") (pinfunction "SDCMD_6") (pintype "bidirectional"))
    )
    (net (code "43") (name "Net-(J3-DATA0{slash}DO)") (class "Default")
      (node (ref "J3") (pin "7") (pinfunction "DATA0/DO_7") (pintype "bidirectional"))
      (node (ref "U2") (pin "2") (pinfunction "SDDATA0_2") (pintype "bidirectional"))
    )
    (net (code "44") (name "Net-(J3-DATA1)") (class "Default")
      (node (ref "J3") (pin "8") (pinfunction "DATA1_8") (pintype "bidirectional"))
      (node (ref "U2") (pin "1") (pinfunction "SDDATA1_1") (pintype "bidirectional"))
    )
    (net (code "45") (name "Net-(J3-DATA2)") (class "Default")
      (node (ref "J3") (pin "1") (pinfunction "DATA2_1") (pintype "bidirectional"))
      (node (ref "U2") (pin "8") (pinfunction "SDDATA2_8") (pintype "bidirectional"))
    )
    (net (code "46") (name "Net-(J3-DATA3{slash}CS)") (class "Default")
      (node (ref "J3") (pin "2") (pinfunction "DATA3/CS_2") (pintype "bidirectional"))
      (node (ref "U2") (pin "7") (pinfunction "SDDATA3_7") (pintype "bidirectional"))
    )
    (net (code "47") (name "Net-(J4-DM)") (class "Default")
      (node (ref "J4") (pin "2") (pinfunction "DM_2") (pintype "bidirectional"))
      (node (ref "R11") (pin "2") (pinfunction "2_2") (pintype "passive"))
    )
    (net (code "48") (name "Net-(J4-DP)") (class "Default")
      (node (ref "J4") (pin "3") (pinfunction "DP_3") (pintype "bidirectional"))
      (node (ref "R14") (pin "2") (pinfunction "2_2") (pintype "passive"))
      (node (ref "R8") (pin "2") (pinfunction "2_2") (pintype "passive"))
    )
    (net (code "49") (name "Net-(J4-ID)") (class "Default")
      (node (ref "J4") (pin "4") (pinfunction "ID_4") (pintype "bidirectional"))
      (node (ref "R7") (pin "2") (pinfunction "2_2") (pintype "passive"))
    )
    (net (code "50") (name "Net-(LED1-PadC)") (class "Default")
      (node (ref "LED1") (pin "C") (pinfunction "C_C") (pintype "passive"))
      (node (ref "R1") (pin "1") (pinfunction "1_1") (pintype "passive"))
    )
    (net (code "51") (name "Net-(LED2-PadA)") (class "Default")
      (node (ref "LED2") (pin "A") (pinfunction "A_A") (pintype "passive"))
      (node (ref "R6") (pin "1") (pinfunction "1_1") (pintype "passive"))
    )
    (net (code "52") (name "Net-(RN1B-1)") (class "Default")
      (node (ref "RN1") (pin "2") (pinfunction "1_2") (pintype "passive"))
      (node (ref "U$5") (pin "P$22") (pinfunction "RXN_P$22") (pintype "bidirectional"))
      (node (ref "X1") (pin "6") (pinfunction "RD-_6") (pintype "passive"))
    )
    (net (code "53") (name "Net-(RN1C-1)") (class "Default")
      (node (ref "RN1") (pin "3") (pinfunction "1_3") (pintype "passive"))
      (node (ref "U$5") (pin "P$21") (pinfunction "TXP_P$21") (pintype "bidirectional"))
      (node (ref "X1") (pin "1") (pinfunction "TD+_1") (pintype "passive"))
    )
    (net (code "54") (name "Net-(RN1D-1)") (class "Default")
      (node (ref "RN1") (pin "4") (pinfunction "1_4") (pintype "passive"))
      (node (ref "U$5") (pin "P$20") (pinfunction "TXN_P$20") (pintype "bidirectional"))
      (node (ref "X1") (pin "2") (pinfunction "TD-_2") (pintype "passive"))
    )
    (net (code "55") (name "Net-(U$2-1)") (class "Default")
      (node (ref "U$2") (pin "P$1") (pinfunction "1_P$1") (pintype "passive"))
      (node (ref "U$3") (pin "P$10") (pinfunction "LX_P$10") (pintype "bidirectional"))
    )
    (net (code "56") (name "Net-(U$3-SS)") (class "Default")
      (node (ref "C8") (pin "1") (pinfunction "1_1") (pintype "passive"))
      (node (ref "U$3") (pin "P$6") (pinfunction "SS_P$6") (pintype "bidirectional"))
    )
    (net (code "57") (name "Net-(U$3-VCC)") (class "Default")
      (node (ref "C2") (pin "1") (pinfunction "1_1") (pintype "passive"))
      (node (ref "U$3") (pin "P$4") (pinfunction "VCC_P$4") (pintype "bidirectional"))
    )
    (net (code "58") (name "Net-(U$5-INT{slash}REFCLK0)") (class "Default")
      (node (ref "R17") (pin "1") (pinfunction "1_1") (pintype "passive"))
      (node (ref "U$5") (pin "P$14") (pinfunction "INT/REFCLK0_P$14") (pintype "bidirectional"))
    )
    (net (code "59") (name "Net-(U$5-LED1{slash}REGOFF)") (class "Default")
      (node (ref "R12") (pin "2") (pinfunction "2_2") (pintype "passive"))
      (node (ref "U$5") (pin "P$3") (pinfunction "LED1/REGOFF_P$3") (pintype "bidirectional"))
    )
    (net (code "60") (name "Net-(U$5-LED2{slash}INTSEL)") (class "Default")
      (node (ref "R13") (pin "2") (pinfunction "2_2") (pintype "passive"))
      (node (ref "R15") (pin "1") (pinfunction "1_1") (pintype "passive"))
      (node (ref "U$5") (pin "P$2") (pinfunction "LED2/INTSEL_P$2") (pintype "bidirectional"))
    )
    (net (code "61") (name "Net-(U$5-RBIAS)") (class "Default")
      (node (ref "R16") (pin "1") (pinfunction "1_1") (pintype "passive"))
      (node (ref "U$5") (pin "P$24") (pinfunction "RBIAS_P$24") (pintype "bidirectional"))
    )
    (net (code "62") (name "Net-(U$5-RXP)") (class "Default")
      (node (ref "RN1") (pin "1") (pinfunction "1_1") (pintype "passive"))
      (node (ref "U$5") (pin "P$23") (pinfunction "RXP_P$23") (pintype "bidirectional"))
      (node (ref "X1") (pin "3") (pinfunction "RD+_3") (pintype "passive"))
    )
    (net (code "63") (name "Net-(U$5-VDDCR)") (class "Default")
      (node (ref "C24") (pin "1") (pinfunction "1_1") (pintype "passive"))
      (node (ref "C25") (pin "1") (pinfunction "1_1") (pintype "passive"))
      (node (ref "U$5") (pin "P$6") (pinfunction "VDDCR_P$6") (pintype "bidirectional"))
    )
    (net (code "64") (name "Net-(U$5-XTAL1{slash}CLKIN)") (class "Default")
      (node (ref "C13") (pin "1") (pinfunction "1_1") (pintype "passive"))
      (node (ref "U$5") (pin "P$5") (pinfunction "XTAL1/CLKIN_P$5") (pintype "bidirectional"))
      (node (ref "U$6") (pin "1") (pinfunction "1_1") (pintype "bidirectional"))
    )
    (net (code "65") (name "Net-(U$5-XTAL2)") (class "Default")
      (node (ref "C6") (pin "1") (pinfunction "1_1") (pintype "passive"))
      (node (ref "U$5") (pin "P$4") (pinfunction "XTAL2_P$4") (pintype "bidirectional"))
      (node (ref "U$6") (pin "3") (pinfunction "3_3") (pintype "bidirectional"))
    )
    (net (code "66") (name "Net-(U1B-VCAP_1)") (class "Default")
      (node (ref "C5") (pin "1") (pinfunction "1_1") (pintype "passive"))
      (node (ref "U1") (pin "49") (pinfunction "VCAP_1_49") (pintype "power_in"))
    )
    (net (code "67") (name "Net-(U1B-VCAP_2)") (class "Default")
      (node (ref "C4") (pin "1") (pinfunction "1_1") (pintype "passive"))
      (node (ref "U1") (pin "73") (pinfunction "VCAP_2_73") (pintype "power_in"))
    )
    (net (code "68") (name "Net-(X1-GA)") (class "Default")
      (node (ref "R12") (pin "1") (pinfunction "1_1") (pintype "passive"))
      (node (ref "X1") (pin "L3") (pinfunction "GA_L3") (pintype "passive"))
    )
    (net (code "69") (name "Net-(X1-YA)") (class "Default")
      (node (ref "R13") (pin "1") (pinfunction "1_1") (pintype "passive"))
      (node (ref "X1") (pin "L1") (pinfunction "YA_L1") (pintype "passive"))
    )
    (net (code "70") (name "unconnected-(SOT1-SHDN-Pad5)") (class "Default")
      (node (ref "SOT1") (pin "5") (pinfunction "SHDN_5") (pintype "bidirectional"))
    )
    (net (code "71") (name "unconnected-(U$3-NC{slash}COMP-PadP$7)") (class "Default")
      (node (ref "U$3") (pin "P$7") (pinfunction "NC/COMP_P$7") (pintype "bidirectional"))
    )
    (net (code "72") (name "unconnected-(U$3-~{RESET}-PadP$8)") (class "Default")
      (node (ref "U$3") (pin "P$8") (pinfunction "~{RESET}_P$8") (pintype "bidirectional"))
    )
    (net (code "73") (name "unconnected-(U1A-PA0-Pad23)") (class "Default")
      (node (ref "U1") (pin "23") (pinfunction "PA0_23") (pintype "passive"))
    )
    (net (code "74") (name "unconnected-(U1A-PA3-Pad26)") (class "Default")
      (node (ref "U1") (pin "26") (pinfunction "PA3_26") (pintype "passive"))
    )
    (net (code "75") (name "unconnected-(U1A-PA5-Pad30)") (class "Default")
      (node (ref "U1") (pin "30") (pinfunction "PA5_30") (pintype "passive"))
    )
    (net (code "76") (name "unconnected-(U1A-PA6-Pad31)") (class "Default")
      (node (ref "U1") (pin "31") (pinfunction "PA6_31") (pintype "passive"))
    )
    (net (code "77") (name "unconnected-(U1A-PA8-Pad67)") (class "Default")
      (node (ref "U1") (pin "67") (pinfunction "PA8_67") (pintype "passive"))
    )
    (net (code "78") (name "unconnected-(U1A-PA9-Pad68)") (class "Default")
      (node (ref "U1") (pin "68") (pinfunction "PA9_68") (pintype "passive"))
    )
    (net (code "79") (name "unconnected-(U1A-PA10-Pad69)") (class "Default")
      (node (ref "U1") (pin "69") (pinfunction "PA10_69") (pintype "passive"))
    )
    (net (code "80") (name "unconnected-(U1A-PB0-Pad35)") (class "Default")
      (node (ref "U1") (pin "35") (pinfunction "PB0_35") (pintype "passive"))
    )
    (net (code "81") (name "unconnected-(U1A-PB1-Pad36)") (class "Default")
      (node (ref "U1") (pin "36") (pinfunction "PB1_36") (pintype "passive"))
    )
    (net (code "82") (name "unconnected-(U1A-PB2-Pad37)") (class "Default")
      (node (ref "U1") (pin "37") (pinfunction "PB2_37") (pintype "passive"))
    )
    (net (code "83") (name "unconnected-(U1A-PB4-Pad90)") (class "Default")
      (node (ref "U1") (pin "90") (pinfunction "PB4_90") (pintype "passive"))
    )
    (net (code "84") (name "unconnected-(U1A-PB5-Pad91)") (class "Default")
      (node (ref "U1") (pin "91") (pinfunction "PB5_91") (pintype "passive"))
    )
    (net (code "85") (name "unconnected-(U1A-PB8-Pad95)") (class "Default")
      (node (ref "U1") (pin "95") (pinfunction "PB8_95") (pintype "passive"))
    )
    (net (code "86") (name "unconnected-(U1A-PB9-Pad96)") (class "Default")
      (node (ref "U1") (pin "96") (pinfunction "PB9_96") (pintype "passive"))
    )
    (net (code "87") (name "unconnected-(U1A-PB10-Pad47)") (class "Default")
      (node (ref "U1") (pin "47") (pinfunction "PB10_47") (pintype "passive"))
    )
    (net (code "88") (name "unconnected-(U1A-PB14-Pad53)") (class "Default")
      (node (ref "U1") (pin "53") (pinfunction "PB14_53") (pintype "passive"))
    )
    (net (code "89") (name "unconnected-(U1A-PB15-Pad54)") (class "Default")
      (node (ref "U1") (pin "54") (pinfunction "PB15_54") (pintype "passive"))
    )
    (net (code "90") (name "unconnected-(U1A-PC0-Pad15)") (class "Default")
      (node (ref "U1") (pin "15") (pinfunction "PC0_15") (pintype "passive"))
    )
    (net (code "91") (name "unconnected-(U1A-PC2-Pad17)") (class "Default")
      (node (ref "U1") (pin "17") (pinfunction "PC2_17") (pintype "passive"))
    )
    (net (code "92") (name "unconnected-(U1A-PC6-Pad63)") (class "Default")
      (node (ref "U1") (pin "63") (pinfunction "PC6_63") (pintype "passive"))
    )
    (net (code "93") (name "unconnected-(U1A-PC7-Pad64)") (class "Default")
      (node (ref "U1") (pin "64") (pinfunction "PC7_64") (pintype "passive"))
    )
    (net (code "94") (name "unconnected-(U1A-PC13-Pad7)") (class "Default")
      (node (ref "U1") (pin "7") (pinfunction "PC13_7") (pintype "passive"))
    )
    (net (code "95") (name "unconnected-(U1A-PC14-Pad8)") (class "Default")
      (node (ref "U1") (pin "8") (pinfunction "PC14_8") (pintype "passive"))
    )
    (net (code "96") (name "unconnected-(U1A-PC15-Pad9)") (class "Default")
      (node (ref "U1") (pin "9") (pinfunction "PC15_9") (pintype "passive"))
    )
    (net (code "97") (name "unconnected-(U1A-PD3-Pad84)") (class "Default")
      (node (ref "U1") (pin "84") (pinfunction "PD3_84") (pintype "passive"))
    )
    (net (code "98") (name "unconnected-(U1A-PD4-Pad85)") (class "Default")
      (node (ref "U1") (pin "85") (pinfunction "PD4_85") (pintype "passive"))
    )
    (net (code "99") (name "unconnected-(U1A-PD5-Pad86)") (class "Default")
      (node (ref "U1") (pin "86") (pinfunction "PD5_86") (pintype "passive"))
    )
    (net (code "100") (name "unconnected-(U1A-PD6-Pad87)") (class "Default")
      (node (ref "U1") (pin "87") (pinfunction "PD6_87") (pintype "passive"))
    )
    (net (code "101") (name "unconnected-(U1A-PD7-Pad88)") (class "Default")
      (node (ref "U1") (pin "88") (pinfunction "PD7_88") (pintype "passive"))
    )
    (net (code "102") (name "unconnected-(U1A-PD8-Pad55)") (class "Default")
      (node (ref "U1") (pin "55") (pinfunction "PD8_55") (pintype "passive"))
    )
    (net (code "103") (name "unconnected-(U1A-PD9-Pad56)") (class "Default")
      (node (ref "U1") (pin "56") (pinfunction "PD9_56") (pintype "passive"))
    )
    (net (code "104") (name "unconnected-(U1A-PD11-Pad58)") (class "Default")
      (node (ref "U1") (pin "58") (pinfunction "PD11_58") (pintype "passive"))
    )
    (net (code "105") (name "unconnected-(U1A-PD12-Pad59)") (class "Default")
      (node (ref "U1") (pin "59") (pinfunction "PD12_59") (pintype "passive"))
    )
    (net (code "106") (name "unconnected-(U1A-PD14-Pad61)") (class "Default")
      (node (ref "U1") (pin "61") (pinfunction "PD14_61") (pintype "passive"))
    )
    (net (code "107") (name "unconnected-(U1A-PD15-Pad62)") (class "Default")
      (node (ref "U1") (pin "62") (pinfunction "PD15_62") (pintype "passive"))
    )
    (net (code "108") (name "unconnected-(U1A-PE0-Pad97)") (class "Default")
      (node (ref "U1") (pin "97") (pinfunction "PE0_97") (pintype "passive"))
    )
    (net (code "109") (name "unconnected-(U1A-PE1-Pad98)") (class "Default")
      (node (ref "U1") (pin "98") (pinfunction "PE1_98") (pintype "passive"))
    )
    (net (code "110") (name "unconnected-(U1A-PE2-Pad1)") (class "Default")
      (node (ref "U1") (pin "1") (pinfunction "PE2_1") (pintype "passive"))
    )
    (net (code "111") (name "unconnected-(U1A-PE3-Pad2)") (class "Default")
      (node (ref "U1") (pin "2") (pinfunction "PE3_2") (pintype "passive"))
    )
    (net (code "112") (name "unconnected-(U1A-PE4-Pad3)") (class "Default")
      (node (ref "U1") (pin "3") (pinfunction "PE4_3") (pintype "passive"))
    )
    (net (code "113") (name "unconnected-(U1A-PE5-Pad4)") (class "Default")
      (node (ref "U1") (pin "4") (pinfunction "PE5_4") (pintype "passive"))
    )
    (net (code "114") (name "unconnected-(U1A-PE7-Pad38)") (class "Default")
      (node (ref "U1") (pin "38") (pinfunction "PE7_38") (pintype "passive"))
    )
    (net (code "115") (name "unconnected-(U1A-PE8-Pad39)") (class "Default")
      (node (ref "U1") (pin "39") (pinfunction "PE8_39") (pintype "passive"))
    )
    (net (code "116") (name "unconnected-(U1A-PE9-Pad40)") (class "Default")
      (node (ref "U1") (pin "40") (pinfunction "PE9_40") (pintype "passive"))
    )
    (net (code "117") (name "unconnected-(U1A-PE10-Pad41)") (class "Default")
      (node (ref "U1") (pin "41") (pinfunction "PE10_41") (pintype "passive"))
    )
    (net (code "118") (name "unconnected-(U1A-PE11-Pad42)") (class "Default")
      (node (ref "U1") (pin "42") (pinfunction "PE11_42") (pintype "passive"))
    )
    (net (code "119") (name "unconnected-(U1A-PE12-Pad43)") (class "Default")
      (node (ref "U1") (pin "43") (pinfunction "PE12_43") (pintype "passive"))
    )
    (net (code "120") (name "unconnected-(U1A-PE13-Pad44)") (class "Default")
      (node (ref "U1") (pin "44") (pinfunction "PE13_44") (pintype "passive"))
    )
    (net (code "121") (name "unconnected-(U1A-PE14-Pad45)") (class "Default")
      (node (ref "U1") (pin "45") (pinfunction "PE14_45") (pintype "passive"))
    )
    (net (code "122") (name "unconnected-(U1A-PE15-Pad46)") (class "Default")
      (node (ref "U1") (pin "46") (pinfunction "PE15_46") (pintype "passive"))
    )
    (net (code "123") (name "unconnected-(U1A-PH1-Pad13)") (class "Default")
      (node (ref "U1") (pin "13") (pinfunction "PH1_13") (pintype "passive"))
    )
    (net (code "124") (name "unconnected-(U2-ESD1-Pad4)") (class "Default")
      (node (ref "U2") (pin "4") (pinfunction "ESD1_4") (pintype "bidirectional"))
    )
    (net (code "125") (name "unconnected-(U2-ESD1-Pad13)") (class "Default")
      (node (ref "U2") (pin "13") (pinfunction "ESD1_13") (pintype "bidirectional"))
    )
    (net (code "126") (name "unconnected-(U2-ESD3-Pad5)") (class "Default")
      (node (ref "U2") (pin "5") (pinfunction "ESD3_5") (pintype "bidirectional"))
    )
    (net (code "127") (name "unconnected-(X1-CT-Pad4)") (class "Default")
      (node (ref "X1") (pin "4") (pinfunction "CT_4") (pintype "passive"))
    )
  )
)
